# STM32_microcontroller_RF.net
KiCad netlist of a schematic drawn in Altium Designer
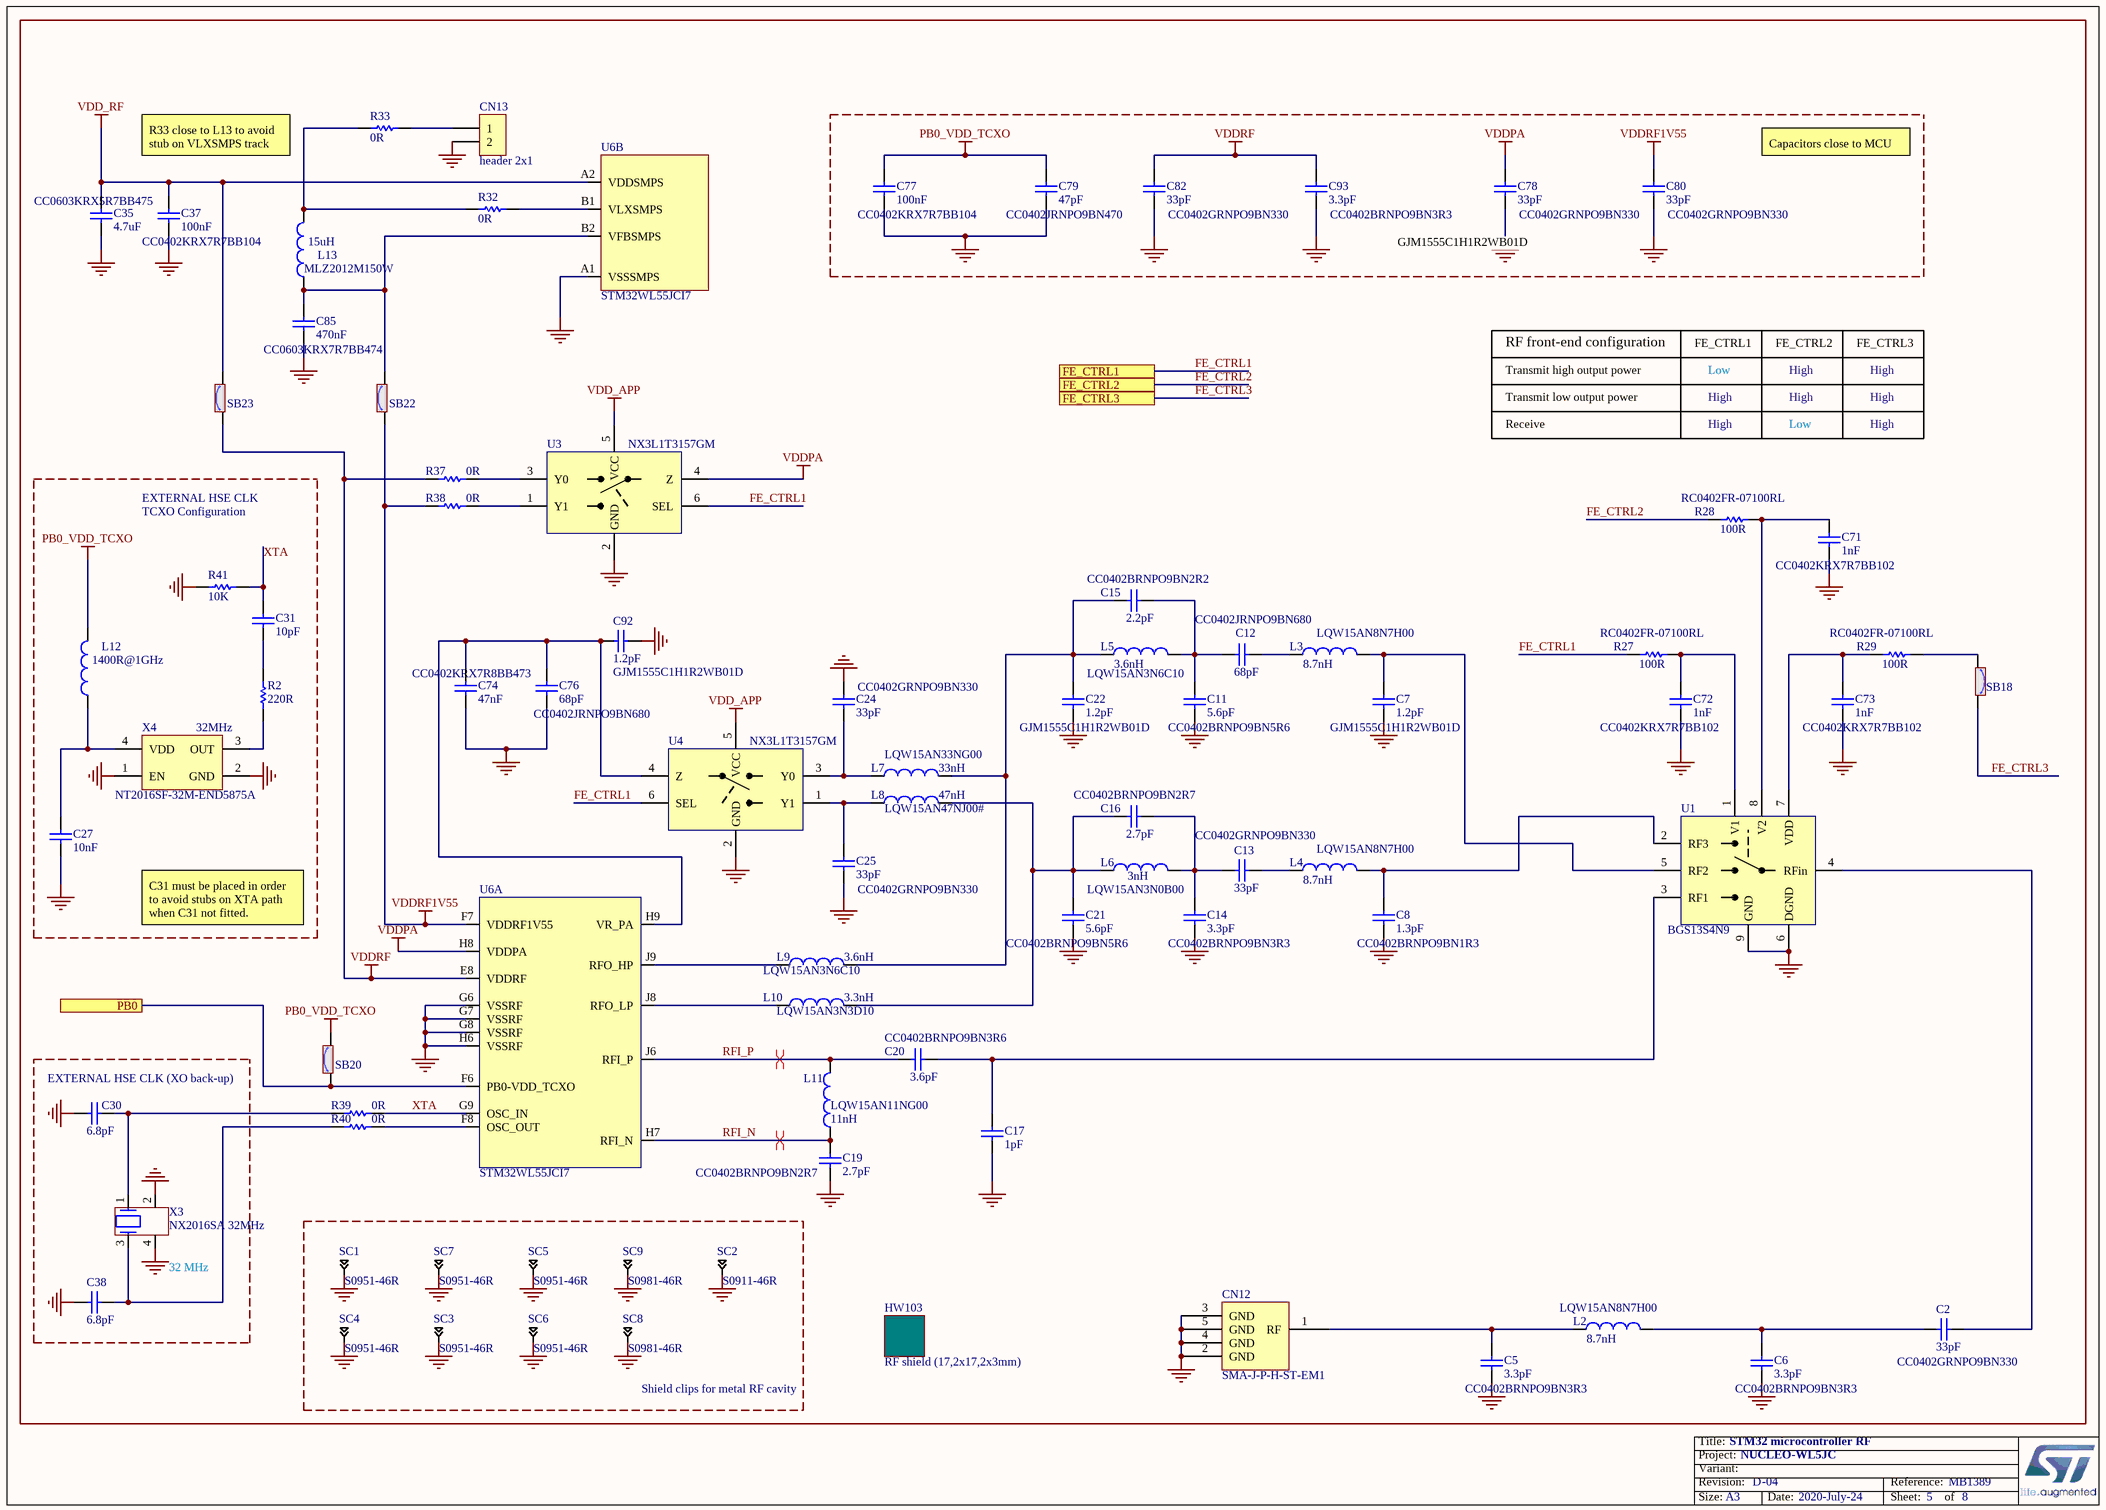
[diagram p0: STM32_microcontroller_RF.SchDoc]

(export (version "E")
  (design (tool "Eeschema 10.0.6"))
  (components
    (comp (ref "C2")
      (value "33pF")
      (footprint "C0402")
      (description "Capacitor, MLCC, 33pF, 50V, NPO, +/-2%, 0402, T=0,5mm")
      (fields
        (field (name "INTERNAL_PART_NUMBER") "MCD-01784")
        (field (name "MANUFACTURER_PART_NUMBER") "CC0402GRNPO9BN330")
        (field (name "MANUFACTURER") "YAGEO")
        (field (name "PROVIDED_BY") "SUBCO")
      )
      (libsource (lib "MCD_PARTS_database") (part "Capacitor"))
    )
    (comp (ref "C5")
      (value "3.3pF")
      (footprint "C0402")
      (description "Capacitor, MLCC, 3.3pF, 50V, NPO, +/-0.1pF, 0402, T=0,5mm")
      (fields
        (field (name "INTERNAL_PART_NUMBER") "MCD-01775")
        (field (name "MANUFACTURER_PART_NUMBER") "CC0402BRNPO9BN3R3")
        (field (name "MANUFACTURER") "YAGEO")
        (field (name "PROVIDED_BY") "SUBCO")
      )
      (libsource (lib "MCD_PARTS_database") (part "Capacitor"))
    )
    (comp (ref "C6")
      (value "3.3pF")
      (footprint "C0402")
      (description "Capacitor, MLCC, 3.3pF, 50V, NPO, +/-0.1pF, 0402, T=0,5mm")
      (fields
        (field (name "INTERNAL_PART_NUMBER") "MCD-01775")
        (field (name "MANUFACTURER_PART_NUMBER") "CC0402BRNPO9BN3R3")
        (field (name "MANUFACTURER") "YAGEO")
        (field (name "PROVIDED_BY") "SUBCO")
      )
      (libsource (lib "MCD_PARTS_database") (part "Capacitor"))
    )
    (comp (ref "C7")
      (value "1.2pF")
      (footprint "C0402")
      (description "Capacitor, High Q type for high frequency and high power, SMD, 1.2pF, 50V, 0,05pf, 0402")
      (fields
        (field (name "INTERNAL_PART_NUMBER") "MCD-02065")
        (field (name "MANUFACTURER") "MURATA")
        (field (name "MANUFACTURER_PART_NUMBER") "GJM1555C1H1R2WB01D")
      )
      (libsource (lib "MCD_PARTS_database") (part "Capacitor"))
    )
    (comp (ref "C8")
      (value "1.3pF")
      (footprint "C0402")
      (description "Capacitor, MLCC, 1.3pF, 50V, NPO, +/-0.1pF, 0402, T=0,5mm")
      (fields
        (field (name "INTERNAL_PART_NUMBER") "MCD-01772")
        (field (name "MANUFACTURER_PART_NUMBER") "CC0402BRNPO9BN1R3")
        (field (name "MANUFACTURER") "YAGEO")
        (field (name "PROVIDED_BY") "SUBCO")
      )
      (libsource (lib "MCD_PARTS_database") (part "Capacitor"))
    )
    (comp (ref "C11")
      (value "5.6pF")
      (footprint "C0402")
      (description "Capacitor, MLCC, 5.6pF, 50V, NPO, +/- 0.1pF, 0402, T=0,5mm")
      (fields
        (field (name "INTERNAL_PART_NUMBER") "MCD-01374")
        (field (name "MANUFACTURER") "YAGEO")
        (field (name "MANUFACTURER_PART_NUMBER") "CC0402BRNPO9BN5R6")
      )
      (libsource (lib "MCD_PARTS_database") (part "Capacitor"))
    )
    (comp (ref "C12")
      (value "68pF")
      (footprint "C0402")
      (description "Capacitor, MLCC, 68pF, 50V, NPO, +/-5%, 0402, T=0,5mm")
      (fields
        (field (name "INTERNAL_PART_NUMBER") "MCD-01604")
        (field (name "MANUFACTURER") "YAGEO")
        (field (name "MANUFACTURER_PART_NUMBER") "CC0402JRNPO9BN680")
      )
      (libsource (lib "MCD_PARTS_database") (part "Capacitor"))
    )
    (comp (ref "C13")
      (value "33pF")
      (footprint "C0402")
      (description "Capacitor, MLCC, 33pF, 50V, NPO, +/-2%, 0402, T=0,5mm")
      (fields
        (field (name "INTERNAL_PART_NUMBER") "MCD-01784")
        (field (name "MANUFACTURER_PART_NUMBER") "CC0402GRNPO9BN330")
        (field (name "MANUFACTURER") "YAGEO")
        (field (name "PROVIDED_BY") "SUBCO")
      )
      (libsource (lib "MCD_PARTS_database") (part "Capacitor"))
    )
    (comp (ref "C14")
      (value "3.3pF")
      (footprint "C0402")
      (description "Capacitor, MLCC, 3.3pF, 50V, NPO, +/-0.1pF, 0402, T=0,5mm")
      (fields
        (field (name "INTERNAL_PART_NUMBER") "MCD-01775")
        (field (name "MANUFACTURER_PART_NUMBER") "CC0402BRNPO9BN3R3")
        (field (name "MANUFACTURER") "YAGEO")
        (field (name "PROVIDED_BY") "SUBCO")
      )
      (libsource (lib "MCD_PARTS_database") (part "Capacitor"))
    )
    (comp (ref "C15")
      (value "2.2pF")
      (footprint "C0402")
      (description "Capacitor, MLCC, 2.2pF, 50V, NPO, +/-0.1pF, 0402, T=0,5mm")
      (fields
        (field (name "INTERNAL_PART_NUMBER") "MCD-01773")
        (field (name "MANUFACTURER") "YAGEO")
        (field (name "MANUFACTURER_PART_NUMBER") "CC0402BRNPO9BN2R2")
      )
      (libsource (lib "MCD_PARTS_database") (part "Capacitor"))
    )
    (comp (ref "C16")
      (value "2.7pF")
      (footprint "C0402")
      (description "Capacitor, MLCC, 2.7pF, 50V, NPO, +/-0.1pF, 0402, T=0,5mm")
      (fields
        (field (name "INTERNAL_PART_NUMBER") "MCD-01774")
        (field (name "MANUFACTURER_PART_NUMBER") "CC0402BRNPO9BN2R7")
        (field (name "MANUFACTURER") "YAGEO")
        (field (name "PROVIDED_BY") "SUBCO")
      )
      (libsource (lib "MCD_PARTS_database") (part "Capacitor"))
    )
    (comp (ref "C17")
      (value "1pF")
      (footprint "C0402")
      (description "Capacitor, MLCC, 1pF, 50V, NPO, +/-0.1pF, 0402, T=0,5mm")
      (fields (field (name "INTERNAL_PART_NUMBER") "MCD-01600") (field (name "MANUFACTURER") "YAGEO"))
      (libsource (lib "MCD_PARTS_database") (part "Capacitor"))
    )
    (comp (ref "C19")
      (value "2.7pF")
      (footprint "C0402")
      (description "Capacitor, MLCC, 2.7pF, 50V, NPO, +/-0.1pF, 0402, T=0,5mm")
      (fields
        (field (name "INTERNAL_PART_NUMBER") "MCD-01774")
        (field (name "MANUFACTURER_PART_NUMBER") "CC0402BRNPO9BN2R7")
        (field (name "MANUFACTURER") "YAGEO")
        (field (name "PROVIDED_BY") "SUBCO")
      )
      (libsource (lib "MCD_PARTS_database") (part "Capacitor"))
    )
    (comp (ref "C20")
      (value "3.6pF")
      (footprint "C0402")
      (description "Capacitor, MLCC, 3.6pF, 50V, NPO, +/-0.1pF, 0402, T=0,5mm")
      (fields
        (field (name "INTERNAL_PART_NUMBER") "MCD-01776")
        (field (name "MANUFACTURER_PART_NUMBER") "CC0402BRNPO9BN3R6")
        (field (name "MANUFACTURER") "YAGEO")
        (field (name "PROVIDED_BY") "SUBCO")
      )
      (libsource (lib "MCD_PARTS_database") (part "Capacitor"))
    )
    (comp (ref "C21")
      (value "5.6pF")
      (footprint "C0402")
      (description "Capacitor, MLCC, 5.6pF, 50V, NPO, +/- 0.1pF, 0402, T=0,5mm")
      (fields
        (field (name "INTERNAL_PART_NUMBER") "MCD-01374")
        (field (name "MANUFACTURER_PART_NUMBER") "CC0402BRNPO9BN5R6")
        (field (name "MANUFACTURER") "YAGEO")
        (field (name "PROVIDED_BY") "SUBCO")
      )
      (libsource (lib "MCD_PARTS_database") (part "Capacitor"))
    )
    (comp (ref "C22")
      (value "1.2pF")
      (footprint "C0402")
      (description "Capacitor, High Q type for high frequency and high power, SMD, 1.2pF, 50V, 0,05pf, 0402")
      (fields
        (field (name "INTERNAL_PART_NUMBER") "MCD-02065")
        (field (name "MANUFACTURER") "MURATA")
        (field (name "MANUFACTURER_PART_NUMBER") "GJM1555C1H1R2WB01D")
      )
      (libsource (lib "MCD_PARTS_database") (part "Capacitor"))
    )
    (comp (ref "C24")
      (value "33pF")
      (footprint "C0402")
      (description "Capacitor, MLCC, 33pF, 50V, NPO, +/-2%, 0402, T=0,5mm")
      (fields
        (field (name "INTERNAL_PART_NUMBER") "MCD-01784")
        (field (name "MANUFACTURER_PART_NUMBER") "CC0402GRNPO9BN330")
        (field (name "MANUFACTURER") "YAGEO")
        (field (name "PROVIDED_BY") "SUBCO")
      )
      (libsource (lib "MCD_PARTS_database") (part "Capacitor"))
    )
    (comp (ref "C25")
      (value "33pF")
      (footprint "C0402")
      (description "Capacitor, MLCC, 33pF, 50V, NPO, +/-2%, 0402, T=0,5mm")
      (fields
        (field (name "INTERNAL_PART_NUMBER") "MCD-01784")
        (field (name "MANUFACTURER_PART_NUMBER") "CC0402GRNPO9BN330")
        (field (name "MANUFACTURER") "YAGEO")
        (field (name "PROVIDED_BY") "SUBCO")
      )
      (libsource (lib "MCD_PARTS_database") (part "Capacitor"))
    )
    (comp (ref "C27")
      (value "10nF")
      (footprint "C0402")
      (description "Capacitor, MLCC, 10nF, 16V, X7R, 10%, 0402, T=0.5mm")
      (fields
        (field (name "INTERNAL_PART_NUMBER") "MCD-00011")
        (field (name "MANUFACTURER_PART_NUMBER") "CC0402KRX7R7BB103")
        (field (name "PROVIDED_BY") "SUBCO")
      )
      (libsource (lib "MCD_PARTS_database") (part "Capacitor"))
    )
    (comp (ref "C30")
      (value "6.8pF")
      (footprint "C0402")
      (description "Capacitor, MLCC, 6.8pF, 50V, NPO, +-0.25pF, 0402, T=0.5mm")
      (fields
        (field (name "INTERNAL_PART_NUMBER") "MCD-00674")
        (field (name "MANUFACTURER_PART_NUMBER") "CC0402CRNPO9BN6R8")
        (field (name "PROVIDED_BY") "SUBCO")
      )
      (libsource (lib "MCD_PARTS_database") (part "Capacitor"))
    )
    (comp (ref "C31")
      (value "10pF")
      (footprint "C0402")
      (description "Capacitor, MLCC, 10pF, 50V, NPO, +/-5%, 0402, T=0,5mm")
      (fields (field (name "INTERNAL_PART_NUMBER") "MCD-00015") (field (name "MANUFACTURER") "YAGEO"))
      (libsource (lib "MCD_PARTS_database") (part "Capacitor"))
    )
    (comp (ref "C35")
      (value "4.7uF")
      (footprint "C0603")
      (description "Capacitor, MLCC, 4.7uF, 16V, X5R, 10%, 0603, T=0.8mm")
      (fields
        (field (name "INTERNAL_PART_NUMBER") "MCD-00009")
        (field (name "MANUFACTURER_PART_NUMBER") "CC0603KRX5R7BB475")
        (field (name "MANUFACTURER") "YAGEO")
        (field (name "PROVIDED_BY") "SUBCO")
      )
      (libsource (lib "MCD_PARTS_database") (part "Capacitor"))
    )
    (comp (ref "C37")
      (value "100nF")
      (footprint "C0402")
      (description "Capacitor, MLCC, 100nF, 16V, X7R, 10%, 0402, T=0,5mm")
      (fields
        (field (name "INTERNAL_PART_NUMBER") "MCD-00102")
        (field (name "MANUFACTURER_PART_NUMBER") "CC0402KRX7R7BB104")
        (field (name "MANUFACTURER") "YAGEO")
        (field (name "PROVIDED_BY") "SUBCO")
      )
      (libsource (lib "MCD_PARTS_database") (part "Capacitor"))
    )
    (comp (ref "C38")
      (value "6.8pF")
      (footprint "C0402")
      (description "Capacitor, MLCC, 6.8pF, 50V, NPO, +-0.25pF, 0402, T=0.5mm")
      (fields
        (field (name "INTERNAL_PART_NUMBER") "MCD-00674")
        (field (name "MANUFACTURER_PART_NUMBER") "CC0402CRNPO9BN6R8")
        (field (name "PROVIDED_BY") "SUBCO")
      )
      (libsource (lib "MCD_PARTS_database") (part "Capacitor"))
    )
    (comp (ref "C71")
      (value "1nF")
      (footprint "C0402")
      (description "Capacitor, MLCC, 1nF, 16V, X7R, 10%, 0402, T=0.5mm")
      (fields
        (field (name "INTERNAL_PART_NUMBER") "MCD-00198")
        (field (name "MANUFACTURER_PART_NUMBER") "CC0402KRX7R7BB102")
        (field (name "MANUFACTURER") "YAGEO")
        (field (name "PROVIDED_BY") "SUBCO")
      )
      (libsource (lib "MCD_PARTS_database") (part "Capacitor"))
    )
    (comp (ref "C72")
      (value "1nF")
      (footprint "C0402")
      (description "Capacitor, MLCC, 1nF, 16V, X7R, 10%, 0402, T=0.5mm")
      (fields
        (field (name "INTERNAL_PART_NUMBER") "MCD-00198")
        (field (name "MANUFACTURER_PART_NUMBER") "CC0402KRX7R7BB102")
        (field (name "MANUFACTURER") "YAGEO")
        (field (name "PROVIDED_BY") "SUBCO")
      )
      (libsource (lib "MCD_PARTS_database") (part "Capacitor"))
    )
    (comp (ref "C73")
      (value "1nF")
      (footprint "C0402")
      (description "Capacitor, MLCC, 1nF, 16V, X7R, 10%, 0402, T=0.5mm")
      (fields
        (field (name "INTERNAL_PART_NUMBER") "MCD-00198")
        (field (name "MANUFACTURER_PART_NUMBER") "CC0402KRX7R7BB102")
        (field (name "MANUFACTURER") "YAGEO")
        (field (name "PROVIDED_BY") "SUBCO")
      )
      (libsource (lib "MCD_PARTS_database") (part "Capacitor"))
    )
    (comp (ref "C74")
      (value "47nF")
      (footprint "C0402")
      (description "Capacitor, MLCC, 47nF, 25V, X7R, +-10%, 0402, T=0,5mm")
      (fields
        (field (name "INTERNAL_PART_NUMBER") "MCD-01605")
        (field (name "MANUFACTURER_PART_NUMBER") "CC0402KRX7R8BB473")
        (field (name "MANUFACTURER") "YAGEO")
        (field (name "PROVIDED_BY") "SUBCO")
      )
      (libsource (lib "MCD_PARTS_database") (part "Capacitor"))
    )
    (comp (ref "C76")
      (value "68pF")
      (footprint "C0402")
      (description "Capacitor, MLCC, 68pF, 50V, NPO, +-5%, 0402, T=0,5mm")
      (fields
        (field (name "INTERNAL_PART_NUMBER") "MCD-01604")
        (field (name "MANUFACTURER_PART_NUMBER") "CC0402JRNPO9BN680")
        (field (name "MANUFACTURER") "YAGEO")
        (field (name "PROVIDED_BY") "SUBCO")
      )
      (libsource (lib "MCD_PARTS_database") (part "Capacitor"))
    )
    (comp (ref "C77")
      (value "100nF")
      (footprint "C0402")
      (description "Capacitor, MLCC, 100nF, 16V, X7R, 10%, 0402, T=0,5mm")
      (fields
        (field (name "INTERNAL_PART_NUMBER") "MCD-00102")
        (field (name "MANUFACTURER_PART_NUMBER") "CC0402KRX7R7BB104")
        (field (name "MANUFACTURER") "YAGEO")
        (field (name "PROVIDED_BY") "SUBCO")
      )
      (libsource (lib "MCD_PARTS_database") (part "Capacitor"))
    )
    (comp (ref "C78")
      (value "33pF")
      (footprint "C0402")
      (description "Capacitor, MLCC, 33pF, 50V, NPO, +/-2%, 0402, T=0,5mm")
      (fields
        (field (name "INTERNAL_PART_NUMBER") "MCD-01784")
        (field (name "MANUFACTURER_PART_NUMBER") "CC0402GRNPO9BN330")
        (field (name "MANUFACTURER") "YAGEO")
        (field (name "PROVIDED_BY") "SUBCO")
      )
      (libsource (lib "MCD_PARTS_database") (part "Capacitor"))
    )
    (comp (ref "C79")
      (value "47pF")
      (footprint "C0402")
      (description "Capacitor, MLCC, 147pF, 50V, NPO, +-5%, 0402, T=0,5mm")
      (fields
        (field (name "INTERNAL_PART_NUMBER") "MCD-01603")
        (field (name "MANUFACTURER_PART_NUMBER") "CC0402JRNPO9BN470")
        (field (name "MANUFACTURER") "YAGEO")
        (field (name "PROVIDED_BY") "SUBCO")
      )
      (libsource (lib "MCD_PARTS_database") (part "Capacitor"))
    )
    (comp (ref "C80")
      (value "33pF")
      (footprint "C0402")
      (description "Capacitor, MLCC, 33pF, 50V, NPO, +/-2%, 0402, T=0,5mm")
      (fields
        (field (name "INTERNAL_PART_NUMBER") "MCD-01784")
        (field (name "MANUFACTURER_PART_NUMBER") "CC0402GRNPO9BN330")
        (field (name "MANUFACTURER") "YAGEO")
        (field (name "PROVIDED_BY") "SUBCO")
      )
      (libsource (lib "MCD_PARTS_database") (part "Capacitor"))
    )
    (comp (ref "C82")
      (value "33pF")
      (footprint "C0402")
      (description "Capacitor, MLCC, 33pF, 50V, NPO, +/-2%, 0402, T=0,5mm")
      (fields
        (field (name "INTERNAL_PART_NUMBER") "MCD-01784")
        (field (name "MANUFACTURER_PART_NUMBER") "CC0402GRNPO9BN330")
        (field (name "MANUFACTURER") "YAGEO")
        (field (name "PROVIDED_BY") "SUBCO")
      )
      (libsource (lib "MCD_PARTS_database") (part "Capacitor"))
    )
    (comp (ref "C85")
      (value "470nF")
      (footprint "C0603")
      (description "Capacitor, MLCC, 470nF, 16V, X7R, 10%, 0603, T=0.8mm")
      (fields
        (field (name "INTERNAL_PART_NUMBER") "MCD-01006")
        (field (name "MANUFACTURER_PART_NUMBER") "CC0603KRX7R7BB474")
        (field (name "MANUFACTURER") "YAGEO")
        (field (name "PROVIDED_BY") "SUBCO")
      )
      (libsource (lib "MCD_PARTS_database") (part "Capacitor"))
    )
    (comp (ref "C92")
      (value "1.2pF")
      (footprint "C0402")
      (description "Capacitor, High Q type for high frequency and high power, SMD, 1.2pF, 50V, 0,05pf, 0402")
      (fields
        (field (name "INTERNAL_PART_NUMBER") "MCD-02065")
        (field (name "MANUFACTURER") "MURATA")
        (field (name "MANUFACTURER_PART_NUMBER") "GJM1555C1H1R2WB01D")
      )
      (libsource (lib "MCD_PARTS_database") (part "Capacitor"))
    )
    (comp (ref "C93")
      (value "3.3pF")
      (footprint "C0402")
      (description "Capacitor, MLCC, 3.3pF, 50V, NPO, +/-0.1pF, 0402, T=0,5mm")
      (fields
        (field (name "INTERNAL_PART_NUMBER") "MCD-01775")
        (field (name "MANUFACTURER") "YAGEO")
        (field (name "MANUFACTURER_PART_NUMBER") "CC0402BRNPO9BN3R3")
      )
      (libsource (lib "MCD_PARTS_database") (part "Capacitor"))
    )
    (comp (ref "CN12")
      (value "SMA-J-P-H-ST-EM1")
      (footprint "CON_SAMTEC_SMA-J-P-X-ST-EM1")
      (description "RF SMA connector PCB edge")
      (fields
        (field (name "INTERNAL_PART_NUMBER") "MCD-00279")
        (field (name "MANUFACTURER") "SAMTEC")
        (field (name "PROVIDED_BY") "SUBCO")
      )
      (libsource (lib "MCD_PARTS_database") (part "SMA-J-P-H-ST-EM1"))
    )
    (comp (ref "CN13")
      (value "header 2x1")
      (footprint "CON_988-JIUBABA_PHFS25-11-02-G0B115-T-1")
      (description "Header, 2x1, 2.54mm, VR, TH, Height 6mm/3mm")
      (fields
        (field (name "INTERNAL_PART_NUMBER") "MCD-00314")
        (field (name "MANUFACTURER_PART_NUMBER") "PHFS25-11-02-G0B115-T-1")
        (field (name "PROVIDED_BY") "SUBCO")
      )
      (libsource (lib "MCD_PARTS_database") (part "Header 2x1"))
    )
    (comp (ref "HW103")
      (value "RF shield (17,2x17,2x3mm)")
      (footprint "SHIELD_RF_ST-CUSTOM_17P2X17P2_H3")
      (description "RF shield (17,2x17,2x3mm), Brass with Sn finishing, Sheet tickness : 0,2mm")
      (fields (field (name "INTERNAL_PART_NUMBER") "MCD-02088") (field (name "BMS_PART_NUMBER") "TBD"))
      (libsource (lib "MCD_PARTS_database") (part "Daughter_Board"))
    )
    (comp (ref "L2")
      (value "8.7nH")
      (footprint "IND_0402_MURATA_LQW15AN_H0P5")
      (description "0402 inductor, 8.7nH +/-3%, 540mA max, 0.14 ohm DC max, Q min = 25")
      (fields
        (field (name "INTERNAL_PART_NUMBER") "MCD-01768")
        (field (name "MANUFACTURER_PART_NUMBER") "LQW15AN8N7H00")
        (field (name "MANUFACTURER") "MURATA")
        (field (name "PROVIDED_BY") "SUBCO")
      )
      (libsource (lib "MCD_PARTS_database") (part "Inductor"))
    )
    (comp (ref "L3")
      (value "8.7nH")
      (footprint "IND_0402_MURATA_LQW15AN_H0P5")
      (description "0402 inductor, 8.7nH +/-3%, 540mA max, 0.14 ohm DC max, Q min = 25")
      (fields
        (field (name "INTERNAL_PART_NUMBER") "MCD-01768")
        (field (name "MANUFACTURER") "MURATA")
        (field (name "MANUFACTURER_PART_NUMBER") "LQW15AN8N7H00")
      )
      (libsource (lib "MCD_PARTS_database") (part "Inductor"))
    )
    (comp (ref "L4")
      (value "8.7nH")
      (footprint "IND_0402_MURATA_LQW15AN_H0P5")
      (description "0402 inductor, 8.7nH +/-3%, 540mA max, 0.14 ohm DC max, Q min = 25")
      (fields
        (field (name "INTERNAL_PART_NUMBER") "MCD-01768")
        (field (name "MANUFACTURER_PART_NUMBER") "LQW15AN8N7H00")
        (field (name "MANUFACTURER") "MURATA")
        (field (name "PROVIDED_BY") "SUBCO")
      )
      (libsource (lib "MCD_PARTS_database") (part "Inductor"))
    )
    (comp (ref "L5")
      (value "3.6nH")
      (footprint "IND_0402_MURATA_LQW15AN_H0P5")
      (description "0402 inductor, 3.6nH +/-0.2nH, 900mA max, 0.04 ohm DC max, Q min = 30")
      (fields
        (field (name "INTERNAL_PART_NUMBER") "MCD-01762")
        (field (name "MANUFACTURER") "MURATA")
        (field (name "MANUFACTURER_PART_NUMBER") "LQW15AN3N6C10")
      )
      (libsource (lib "MCD_PARTS_database") (part "Inductor"))
    )
    (comp (ref "L6")
      (value "3nH")
      (footprint "IND_0402_MURATA_LQW15AN_H0P5")
      (description "0402 inductor, 3nH +-0.1nH, 750mA max, 0.07 ohm DC max, Q min = 20")
      (fields
        (field (name "INTERNAL_PART_NUMBER") "MCD-01922")
        (field (name "MANUFACTURER_PART_NUMBER") "LQW15AN3N0B00")
        (field (name "MANUFACTURER") "MURATA")
        (field (name "PROVIDED_BY") "SUBCO")
      )
      (libsource (lib "MCD_PARTS_database") (part "Inductor"))
    )
    (comp (ref "L7")
      (value "33nH")
      (footprint "IND_0402_MURATA_LQW15AN_H0P5")
      (description "Inductor, 33nH +/-2%, 260mA max , 0.63 ohm DC max, 0402, Q min = 25.")
      (fields
        (field (name "INTERNAL_PART_NUMBER") "MCD-02069")
        (field (name "MANUFACTURER") "MURATA")
        (field (name "MANUFACTURER_PART_NUMBER") "LQW15AN33NG00")
      )
      (libsource (lib "MCD_PARTS_database") (part "Inductor"))
    )
    (comp (ref "L8")
      (value "47nH")
      (footprint "IND_0402_MURATA_LQW15AN2N4C00X")
      (description "Inductor, 47nH, +-5%, 210mA, 1.08ohm DC max, 0402")
      (fields
        (field (name "INTERNAL_PART_NUMBER") "MCD-01609")
        (field (name "MANUFACTURER_PART_NUMBER") "LQW15AN47NJ00#")
        (field (name "MANUFACTURER") "MURATA")
        (field (name "PROVIDED_BY") "SUBCO")
      )
      (libsource (lib "MCD_PARTS_database") (part "Inductor"))
    )
    (comp (ref "L9")
      (value "3.6nH")
      (footprint "IND_0402_MURATA_LQW15AN_H0P5")
      (description "0402 inductor, 3.6nH +/-0.2nH, 900mA max, 0.04 ohm DC max, Q min = 30")
      (fields
        (field (name "INTERNAL_PART_NUMBER") "MCD-01762")
        (field (name "MANUFACTURER_PART_NUMBER") "LQW15AN3N6C10")
        (field (name "MANUFACTURER") "MURATA")
        (field (name "PROVIDED_BY") "SUBCO")
      )
      (libsource (lib "MCD_PARTS_database") (part "Inductor"))
    )
    (comp (ref "L10")
      (value "3.3nH")
      (footprint "IND_0402_MURATA_LQW15AN_H0P5")
      (description "0402 inductor, 3.3nH +-0.5nH, 900mA max, 0.04 ohm DC max, Q min = 30")
      (fields
        (field (name "INTERNAL_PART_NUMBER") "MCD-01761")
        (field (name "MANUFACTURER_PART_NUMBER") "LQW15AN3N3D10")
        (field (name "MANUFACTURER") "MURATA")
        (field (name "PROVIDED_BY") "SUBCO")
      )
      (libsource (lib "MCD_PARTS_database") (part "Inductor"))
    )
    (comp (ref "L11")
      (value "11nH")
      (footprint "IND_0402_MURATA_LQW15AN_H0P5")
      (description "0402 inductor, 11nH +-2%, 500mA max, 0.14 ohm DC max, Q min = 30")
      (fields
        (field (name "INTERNAL_PART_NUMBER") "MCD-01921")
        (field (name "MANUFACTURER_PART_NUMBER") "LQW15AN11NG00")
        (field (name "MANUFACTURER") "MURATA")
        (field (name "PROVIDED_BY") "SUBCO")
      )
      (libsource (lib "MCD_PARTS_database") (part "Inductor"))
    )
    (comp (ref "L12")
      (value "1400R@1GHz")
      (footprint "IND_0402_MURATA_BLM15H_H0P5")
      (description "ferrite bead, 1400ohms at 1GHz, 250mA, 1.1ohms DC max")
      (fields
        (field (name "INTERNAL_PART_NUMBER") "MCD-01610")
        (field (name "MANUFACTURER_PART_NUMBER") "BLM15HG102SN1#")
        (field (name "PROVIDED_BY") "SUBCO")
      )
      (libsource (lib "MCD_PARTS_database") (part "Inductor"))
    )
    (comp (ref "L13")
      (value "15uH")
      (footprint "IND_TDK_MLZ2012M150W")
      (description "MLZ2012 Multilayer Shielded Inductor 15uH, +/-5%")
      (fields
        (field (name "INTERNAL_PART_NUMBER") "MCD-01433")
        (field (name "MANUFACTURER_PART_NUMBER") "MLZ2012M150W")
        (field (name "MANUFACTURER") "TDK")
        (field (name "PROVIDED_BY") "SUBCO")
      )
      (libsource (lib "MCD_PARTS_database") (part "Inductor"))
    )
    (comp (ref "R2")
      (value "220R")
      (footprint "R0402")
      (description "Resistor,220R,0402,1%,1/16W")
      (fields
        (field (name "INTERNAL_PART_NUMBER") "MCD-00427")
        (field (name "MANUFACTURER_PART_NUMBER") "RC0402FR-07220RL")
        (field (name "PROVIDED_BY") "SUBCO")
      )
      (libsource (lib "MCD_PARTS_database") (part "Resistor"))
    )
    (comp (ref "R27")
      (value "100R")
      (footprint "R0402")
      (description "Resistor,100R,0402,1%,1/16W")
      (fields
        (field (name "INTERNAL_PART_NUMBER") "MCD-00119")
        (field (name "MANUFACTURER_PART_NUMBER") "RC0402FR-07100RL")
        (field (name "MANUFACTURER") "YAGEO")
        (field (name "PROVIDED_BY") "SUBCO")
      )
      (libsource (lib "MCD_PARTS_database") (part "Resistor"))
    )
    (comp (ref "R28")
      (value "100R")
      (footprint "R0402")
      (description "Resistor,100R,0402,1%,1/16W")
      (fields
        (field (name "INTERNAL_PART_NUMBER") "MCD-00119")
        (field (name "MANUFACTURER_PART_NUMBER") "RC0402FR-07100RL")
        (field (name "MANUFACTURER") "YAGEO")
        (field (name "PROVIDED_BY") "SUBCO")
      )
      (libsource (lib "MCD_PARTS_database") (part "Resistor"))
    )
    (comp (ref "R29")
      (value "100R")
      (footprint "R0402")
      (description "Resistor,100R,0402,1%,1/16W")
      (fields
        (field (name "INTERNAL_PART_NUMBER") "MCD-00119")
        (field (name "MANUFACTURER_PART_NUMBER") "RC0402FR-07100RL")
        (field (name "MANUFACTURER") "YAGEO")
        (field (name "PROVIDED_BY") "SUBCO")
      )
      (libsource (lib "MCD_PARTS_database") (part "Resistor"))
    )
    (comp (ref "R32")
      (value "0R")
      (footprint "R0402")
      (description "Resistor,0R,0402,5%,1/16W")
      (fields
        (field (name "INTERNAL_PART_NUMBER") "MCD-00052")
        (field (name "MANUFACTURER_PART_NUMBER") "RC0402JR-070RL")
        (field (name "PROVIDED_BY") "SUBCO")
      )
      (libsource (lib "MCD_PARTS_database") (part "Resistor"))
    )
    (comp (ref "R33")
      (value "0R")
      (footprint "R0402")
      (description "Resistor,0R,0402,5%,1/16W")
      (fields
        (field (name "INTERNAL_PART_NUMBER") "MCD-00052")
        (field (name "MANUFACTURER_PART_NUMBER") "RC0402JR-070RL")
        (field (name "PROVIDED_BY") "SUBCO")
      )
      (libsource (lib "MCD_PARTS_database") (part "Resistor"))
    )
    (comp (ref "R37")
      (value "0R")
      (footprint "R0402")
      (description "Resistor,0R,0402,5%,1/16W")
      (fields
        (field (name "INTERNAL_PART_NUMBER") "MCD-00052")
        (field (name "MANUFACTURER_PART_NUMBER") "RC0402JR-070RL")
        (field (name "PROVIDED_BY") "SUBCO")
      )
      (libsource (lib "MCD_PARTS_database") (part "Resistor"))
    )
    (comp (ref "R38")
      (value "0R")
      (footprint "R0402")
      (description "Resistor,0R,0402,5%,1/16W")
      (fields
        (field (name "INTERNAL_PART_NUMBER") "MCD-00052")
        (field (name "MANUFACTURER_PART_NUMBER") "RC0402JR-070RL")
        (field (name "PROVIDED_BY") "SUBCO")
      )
      (libsource (lib "MCD_PARTS_database") (part "Resistor"))
    )
    (comp (ref "R39")
      (value "0R")
      (footprint "R0402")
      (description "Resistor,0R,0402,5%,1/16W")
      (fields
        (field (name "INTERNAL_PART_NUMBER") "MCD-00052")
        (field (name "MANUFACTURER_PART_NUMBER") "RC0402JR-070RL")
        (field (name "PROVIDED_BY") "SUBCO")
      )
      (libsource (lib "MCD_PARTS_database") (part "Resistor"))
    )
    (comp (ref "R40")
      (value "0R")
      (footprint "R0402")
      (description "Resistor,0R,0402,5%,1/16W")
      (fields
        (field (name "INTERNAL_PART_NUMBER") "MCD-00052")
        (field (name "MANUFACTURER_PART_NUMBER") "RC0402JR-070RL")
        (field (name "PROVIDED_BY") "SUBCO")
      )
      (libsource (lib "MCD_PARTS_database") (part "Resistor"))
    )
    (comp (ref "R41")
      (value "10K")
      (footprint "R0402")
      (description "Resistor,10K,0402,1%,1/16W")
      (fields
        (field (name "INTERNAL_PART_NUMBER") "MCD-00053")
        (field (name "MANUFACTURER_PART_NUMBER") "RC0402FR-0710KL")
        (field (name "PROVIDED_BY") "SUBCO")
      )
      (libsource (lib "MCD_PARTS_database") (part "Resistor"))
    )
    (comp (ref "SB18")
      (value "~")
      (footprint "SOLDER-BRIDGE_R0603-0R")
      (description "Solder Bridge ON")
      (fields
        (field (name "INTERNAL_PART_NUMBER") "MCD-00071")
        (field (name "MANUFACTURER_PART_NUMBER") "RC0603JR-070RL")
        (field (name "PROVIDED_BY") "SUBCO")
      )
      (libsource (lib "") (part "SB_ON_1"))
    )
    (comp (ref "SB20")
      (value "~")
      (footprint "SOLDER-BRIDGE_R0603-0R")
      (description "Solder Bridge ON")
      (fields
        (field (name "INTERNAL_PART_NUMBER") "MCD-00071")
        (field (name "MANUFACTURER_PART_NUMBER") "RC0603JR-070RL")
        (field (name "PROVIDED_BY") "SUBCO")
      )
      (libsource (lib "MCD_PARTS_database") (part "SB_ON"))
    )
    (comp (ref "SB22")
      (value "~")
      (footprint "SOLDER-BRIDGE_R0603-0R")
      (description "Solder Bridge ON")
      (fields
        (field (name "INTERNAL_PART_NUMBER") "MCD-00071")
        (field (name "MANUFACTURER_PART_NUMBER") "RC0603JR-070RL")
        (field (name "PROVIDED_BY") "SUBCO")
      )
      (libsource (lib "MCD_PARTS_database") (part "SB_ON"))
    )
    (comp (ref "SB23")
      (value "~")
      (footprint "SOLDER-BRIDGE_R0603-0R")
      (description "Solder Bridge ON")
      (fields
        (field (name "INTERNAL_PART_NUMBER") "MCD-00071")
        (field (name "MANUFACTURER_PART_NUMBER") "RC0603JR-070RL")
        (field (name "PROVIDED_BY") "SUBCO")
      )
      (libsource (lib "MCD_PARTS_database") (part "SB_ON"))
    )
    (comp (ref "SC1")
      (value "S0951-46R")
      (footprint "CLIP_HARWIN_S0951-46R")
      (description "shield clip Harwin S0951-46R to fix RF shielded cavity")
      (fields
        (field (name "INTERNAL_PART_NUMBER") "MCD-01587")
        (field (name "MANUFACTURER") "HARWIN")
        (field (name "PROVIDED_BY") "SUBCO")
      )
      (libsource (lib "MCD_PARTS_database") (part "Shield-clip_S0951-46R"))
    )
    (comp (ref "SC2")
      (value "S0911-46R")
      (description "shield clip Harwin S0911-46R to fix RF shielded cavity - SMT RFI Shield Clip, Compact (T+R)")
      (fields
        (field (name "INTERNAL_PART_NUMBER") "MCD-02165")
        (field (name "MANUFACTURER") "HARWIN")
        (field (name "PROVIDED_BY") "SUBCO")
      )
      (libsource (lib "MCD_PARTS_database") (part "Shield-clip_S0951-46R"))
    )
    (comp (ref "SC3")
      (value "S0951-46R")
      (footprint "CLIP_HARWIN_S0951-46R")
      (description "shield clip Harwin S0951-46R to fix RF shielded cavity")
      (fields
        (field (name "INTERNAL_PART_NUMBER") "MCD-01587")
        (field (name "MANUFACTURER") "HARWIN")
        (field (name "PROVIDED_BY") "SUBCO")
      )
      (libsource (lib "MCD_PARTS_database") (part "Shield-clip_S0951-46R"))
    )
    (comp (ref "SC4")
      (value "S0951-46R")
      (footprint "CLIP_HARWIN_S0951-46R")
      (description "shield clip Harwin S0951-46R to fix RF shielded cavity")
      (fields
        (field (name "INTERNAL_PART_NUMBER") "MCD-01587")
        (field (name "MANUFACTURER") "HARWIN")
        (field (name "PROVIDED_BY") "SUBCO")
      )
      (libsource (lib "MCD_PARTS_database") (part "Shield-clip_S0951-46R"))
    )
    (comp (ref "SC5")
      (value "S0951-46R")
      (footprint "CLIP_HARWIN_S0951-46R")
      (description "shield clip Harwin S0951-46R to fix RF shielded cavity")
      (fields
        (field (name "INTERNAL_PART_NUMBER") "MCD-01587")
        (field (name "MANUFACTURER") "HARWIN")
        (field (name "PROVIDED_BY") "SUBCO")
      )
      (libsource (lib "MCD_PARTS_database") (part "Shield-clip_S0951-46R"))
    )
    (comp (ref "SC6")
      (value "S0951-46R")
      (footprint "CLIP_HARWIN_S0951-46R")
      (description "shield clip Harwin S0951-46R to fix RF shielded cavity")
      (fields
        (field (name "INTERNAL_PART_NUMBER") "MCD-01587")
        (field (name "MANUFACTURER") "HARWIN")
        (field (name "PROVIDED_BY") "SUBCO")
      )
      (libsource (lib "MCD_PARTS_database") (part "Shield-clip_S0951-46R"))
    )
    (comp (ref "SC7")
      (value "S0951-46R")
      (footprint "CLIP_HARWIN_S0951-46R")
      (description "shield clip Harwin S0951-46R to fix RF shielded cavity")
      (fields
        (field (name "INTERNAL_PART_NUMBER") "MCD-01587")
        (field (name "MANUFACTURER") "HARWIN")
        (field (name "PROVIDED_BY") "SUBCO")
      )
      (libsource (lib "MCD_PARTS_database") (part "Shield-clip_S0951-46R"))
    )
    (comp (ref "SC8")
      (value "S0981-46R")
      (description "shield clip Harwin S0981-46R to fix RF shielded cavity - SMT RFI Shield Clip, Corner (T+R)")
      (fields
        (field (name "INTERNAL_PART_NUMBER") "MCD-02164")
        (field (name "MANUFACTURER") "HARWIN")
        (field (name "PROVIDED_BY") "SUBCO")
      )
      (libsource (lib "MCD_PARTS_database") (part "Shield-clip_S0951-46R"))
    )
    (comp (ref "SC9")
      (value "S0981-46R")
      (description "shield clip Harwin S0981-46R to fix RF shielded cavity - SMT RFI Shield Clip, Corner (T+R)")
      (fields
        (field (name "INTERNAL_PART_NUMBER") "MCD-02164")
        (field (name "MANUFACTURER") "HARWIN")
        (field (name "PROVIDED_BY") "SUBCO")
      )
      (libsource (lib "MCD_PARTS_database") (part "Shield-clip_S0951-46R"))
    )
    (comp (ref "U1")
      (value "BGS13S4N9")
      (footprint "ICC_TSNP-9-3_1P1X1P1_P040")
      (description "Wideband RF SP3T Switch")
      (fields
        (field (name "INTERNAL_PART_NUMBER") "MCD-02018")
        (field (name "MANUFACTURER") "INFINEON")
        (field (name "PROVIDED_BY") "SUBCO")
      )
      (libsource (lib "MCD_PARTS_database") (part "BGS13S4N9"))
    )
    (comp (ref "U3")
      (value "NX3L1T3157GM")
      (footprint "ICC_SOT886_XSON6")
      (description "DC switch - Ultra-Low 0.5ohm  SPDT analog switch")
      (fields
        (field (name "INTERNAL_PART_NUMBER") "MCD-01514")
        (field (name "MANUFACTURER") "NXP")
        (field (name "PROVIDED_BY") "SUBCO")
      )
      (libsource (lib "") (part "NX3L1T3157GM_1"))
    )
    (comp (ref "U4")
      (value "NX3L1T3157GM")
      (footprint "ICC_SOT886_XSON6")
      (description "DC switch - Ultra-Low 0.5ohm  SPDT analog switch")
      (fields
        (field (name "INTERNAL_PART_NUMBER") "MCD-01514")
        (field (name "MANUFACTURER") "NXP")
        (field (name "PROVIDED_BY") "SUBCO")
      )
      (libsource (lib "MCD_PARTS_database") (part "NX3L1T3157GM"))
    )
    (comp (ref "U6")
      (value "STM32WL55JCI7")
      (footprint "ICC_UFBGA73_5X5_P050")
      (description "Multiprotocol Wireless 32-bit MCUwith LPWAN Sub-GHz radio solution")
      (fields
        (field (name "INTERNAL_PART_NUMBER") "MCD-01435")
        (field (name "MANUFACTURER") "STMICROELECTRONICS")
      )
      (libsource (lib "MCD_PARTS_database") (part "STM32WL5x_BGA73"))
    )
    (comp (ref "X3")
      (value "NX2016SA 32MHz")
      (footprint "CRY_NX2016SA_4P")
      (description "Crystal 32MHz, 10pF, +-10 ppm, 50ohm max, SMD")
      (fields
        (field (name "INTERNAL_PART_NUMBER") "MCD-01507")
        (field (name "MANUFACTURER_PART_NUMBER") "NX2016SA 32MHz EXS00A-CS06465")
        (field (name "PROVIDED_BY") "SUBCO")
      )
      (libsource (lib "MCD_PARTS_database") (part "XTAL_4_PINS"))
    )
    (comp (ref "X4")
      (value "32MHz")
      (footprint "CRY_NDK_NT2016SB_4P")
      (description "NT2016SF-32M-END5875A")
      (fields
        (field (name "INTERNAL_PART_NUMBER") "MCD-02240")
        (field (name "MANUFACTURER") "NDK")
        (field (name "MANUFACTURER_PART_NUMBER") "NT2016SF-32M-END5875A")
      )
      (libsource (lib "MCD_PARTS_database") (part "NT2016SB"))
    )
  )
  (nets
    (net (code "1") (name "/FE_CTRL1") (class "Default")
      (node (ref "R27") (pin "1") (pinfunction "1_1") (pintype "passive"))
      (node (ref "U3") (pin "6") (pinfunction "SEL_6") (pintype "passive"))
      (node (ref "U4") (pin "6") (pinfunction "SEL_6") (pintype "passive"))
    )
    (net (code "2") (name "/FE_CTRL2") (class "Default")
      (node (ref "R28") (pin "1") (pinfunction "1_1") (pintype "passive"))
    )
    (net (code "3") (name "/FE_CTRL3") (class "Default")
      (node (ref "SB18") (pin "2") (pinfunction "2_2") (pintype "passive"))
    )
    (net (code "4") (name "/PB0") (class "Default")
      (node (ref "SB20") (pin "1") (pinfunction "1_1") (pintype "passive"))
      (node (ref "U6") (pin "F6") (pinfunction "PB0-VDD_TCXO_F6") (pintype "passive"))
    )
    (net (code "5") (name "/RFI_N") (class "Default")
      (node (ref "C19") (pin "2") (pinfunction "2_2") (pintype "passive"))
      (node (ref "L11") (pin "1") (pinfunction "1_1") (pintype "passive"))
      (node (ref "U6") (pin "H7") (pinfunction "RFI_N_H7") (pintype "passive"))
    )
    (net (code "6") (name "/RFI_P") (class "Default")
      (node (ref "C20") (pin "1") (pinfunction "1_1") (pintype "passive"))
      (node (ref "L11") (pin "2") (pinfunction "2_2") (pintype "passive"))
      (node (ref "U6") (pin "J6") (pinfunction "RFI_P_J6") (pintype "passive"))
    )
    (net (code "7") (name "/XTA") (class "Default")
      (node (ref "C31") (pin "2") (pinfunction "2_2") (pintype "passive"))
      (node (ref "R39") (pin "1") (pinfunction "1_1") (pintype "passive"))
      (node (ref "R41") (pin "2") (pinfunction "2_2") (pintype "passive"))
      (node (ref "U6") (pin "G9") (pinfunction "OSC_IN_G9") (pintype "passive"))
    )
    (net (code "8") (name "GND") (class "Default")
      (node (ref "C11") (pin "1") (pinfunction "1_1") (pintype "passive"))
      (node (ref "C14") (pin "1") (pinfunction "1_1") (pintype "passive"))
      (node (ref "C17") (pin "1") (pinfunction "1_1") (pintype "passive"))
      (node (ref "C19") (pin "1") (pinfunction "1_1") (pintype "passive"))
      (node (ref "C21") (pin "1") (pinfunction "1_1") (pintype "passive"))
      (node (ref "C22") (pin "1") (pinfunction "1_1") (pintype "passive"))
      (node (ref "C24") (pin "2") (pinfunction "2_2") (pintype "passive"))
      (node (ref "C25") (pin "1") (pinfunction "1_1") (pintype "passive"))
      (node (ref "C27") (pin "1") (pinfunction "1_1") (pintype "passive"))
      (node (ref "C30") (pin "1") (pinfunction "1_1") (pintype "passive"))
      (node (ref "C35") (pin "1") (pinfunction "1_1") (pintype "passive"))
      (node (ref "C37") (pin "2") (pinfunction "2_2") (pintype "passive"))
      (node (ref "C38") (pin "1") (pinfunction "1_1") (pintype "passive"))
      (node (ref "C5") (pin "1") (pinfunction "1_1") (pintype "passive"))
      (node (ref "C6") (pin "1") (pinfunction "1_1") (pintype "passive"))
      (node (ref "C7") (pin "1") (pinfunction "1_1") (pintype "passive"))
      (node (ref "C71") (pin "1") (pinfunction "1_1") (pintype "passive"))
      (node (ref "C72") (pin "1") (pinfunction "1_1") (pintype "passive"))
      (node (ref "C73") (pin "1") (pinfunction "1_1") (pintype "passive"))
      (node (ref "C74") (pin "1") (pinfunction "1_1") (pintype "passive"))
      (node (ref "C76") (pin "1") (pinfunction "1_1") (pintype "passive"))
      (node (ref "C77") (pin "2") (pinfunction "2_2") (pintype "passive"))
      (node (ref "C78") (pin "1") (pinfunction "1_1") (pintype "passive"))
      (node (ref "C79") (pin "1") (pinfunction "1_1") (pintype "passive"))
      (node (ref "C8") (pin "1") (pinfunction "1_1") (pintype "passive"))
      (node (ref "C80") (pin "1") (pinfunction "1_1") (pintype "passive"))
      (node (ref "C82") (pin "1") (pinfunction "1_1") (pintype "passive"))
      (node (ref "C85") (pin "1") (pinfunction "1_1") (pintype "passive"))
      (node (ref "C92") (pin "1") (pinfunction "1_1") (pintype "passive"))
      (node (ref "C93") (pin "1") (pinfunction "1_1") (pintype "passive"))
      (node (ref "CN12") (pin "2") (pinfunction "GND_2") (pintype "passive"))
      (node (ref "CN12") (pin "3") (pinfunction "GND_3") (pintype "passive"))
      (node (ref "CN12") (pin "4") (pinfunction "GND_4") (pintype "passive"))
      (node (ref "CN12") (pin "5") (pinfunction "GND_5") (pintype "passive"))
      (node (ref "CN13") (pin "2") (pinfunction "2_2") (pintype "passive"))
      (node (ref "R41") (pin "1") (pinfunction "1_1") (pintype "passive"))
      (node (ref "SC1") (pin "1") (pinfunction "1_1") (pintype "passive"))
      (node (ref "SC2") (pin "1") (pinfunction "1_1") (pintype "passive"))
      (node (ref "SC3") (pin "1") (pinfunction "1_1") (pintype "passive"))
      (node (ref "SC4") (pin "1") (pinfunction "1_1") (pintype "passive"))
      (node (ref "SC5") (pin "1") (pinfunction "1_1") (pintype "passive"))
      (node (ref "SC6") (pin "1") (pinfunction "1_1") (pintype "passive"))
      (node (ref "SC7") (pin "1") (pinfunction "1_1") (pintype "passive"))
      (node (ref "SC8") (pin "1") (pinfunction "1_1") (pintype "passive"))
      (node (ref "SC9") (pin "1") (pinfunction "1_1") (pintype "passive"))
      (node (ref "U1") (pin "6") (pinfunction "DGND_6") (pintype "passive"))
      (node (ref "U1") (pin "9") (pinfunction "GND_9") (pintype "passive"))
      (node (ref "U3") (pin "2") (pinfunction "GND_2") (pintype "passive"))
      (node (ref "U4") (pin "2") (pinfunction "GND_2") (pintype "passive"))
      (node (ref "U6") (pin "A1") (pinfunction "VSSSMPS_A1") (pintype "passive"))
      (node (ref "U6") (pin "G6") (pinfunction "VSSRF_G6") (pintype "passive"))
      (node (ref "U6") (pin "G7") (pinfunction "VSSRF_G7") (pintype "passive"))
      (node (ref "U6") (pin "G8") (pinfunction "VSSRF_G8") (pintype "passive"))
      (node (ref "U6") (pin "H6") (pinfunction "VSSRF_H6") (pintype "passive"))
      (node (ref "X3") (pin "2") (pinfunction "2_2") (pintype "passive"))
      (node (ref "X3") (pin "4") (pinfunction "4_4") (pintype "passive"))
      (node (ref "X4") (pin "1") (pinfunction "EN_1") (pintype "passive"))
      (node (ref "X4") (pin "2") (pinfunction "GND_2") (pintype "passive"))
    )
    (net (code "9") (name "Net-(C2-Pad1)") (class "Default")
      (node (ref "C2") (pin "1") (pinfunction "1_1") (pintype "passive"))
      (node (ref "C6") (pin "2") (pinfunction "2_2") (pintype "passive"))
      (node (ref "L2") (pin "2") (pinfunction "2_2") (pintype "passive"))
    )
    (net (code "10") (name "Net-(C11-Pad2)") (class "Default")
      (node (ref "C11") (pin "2") (pinfunction "2_2") (pintype "passive"))
      (node (ref "C12") (pin "1") (pinfunction "1_1") (pintype "passive"))
      (node (ref "C15") (pin "2") (pinfunction "2_2") (pintype "passive"))
      (node (ref "L5") (pin "2") (pinfunction "2_2") (pintype "passive"))
    )
    (net (code "11") (name "Net-(C12-Pad2)") (class "Default")
      (node (ref "C12") (pin "2") (pinfunction "2_2") (pintype "passive"))
      (node (ref "L3") (pin "1") (pinfunction "1_1") (pintype "passive"))
    )
    (net (code "12") (name "Net-(C13-Pad1)") (class "Default")
      (node (ref "C13") (pin "1") (pinfunction "1_1") (pintype "passive"))
      (node (ref "L4") (pin "1") (pinfunction "1_1") (pintype "passive"))
    )
    (net (code "13") (name "Net-(C13-Pad2)") (class "Default")
      (node (ref "C13") (pin "2") (pinfunction "2_2") (pintype "passive"))
      (node (ref "C14") (pin "2") (pinfunction "2_2") (pintype "passive"))
      (node (ref "C16") (pin "1") (pinfunction "1_1") (pintype "passive"))
      (node (ref "L6") (pin "2") (pinfunction "2_2") (pintype "passive"))
    )
    (net (code "14") (name "Net-(C15-Pad1)") (class "Default")
      (node (ref "C15") (pin "1") (pinfunction "1_1") (pintype "passive"))
      (node (ref "C22") (pin "2") (pinfunction "2_2") (pintype "passive"))
      (node (ref "L5") (pin "1") (pinfunction "1_1") (pintype "passive"))
      (node (ref "L7") (pin "2") (pinfunction "2_2") (pintype "passive"))
      (node (ref "L9") (pin "2") (pinfunction "2_2") (pintype "passive"))
    )
    (net (code "15") (name "Net-(C16-Pad2)") (class "Default")
      (node (ref "C16") (pin "2") (pinfunction "2_2") (pintype "passive"))
      (node (ref "C21") (pin "2") (pinfunction "2_2") (pintype "passive"))
      (node (ref "L10") (pin "2") (pinfunction "2_2") (pintype "passive"))
      (node (ref "L6") (pin "1") (pinfunction "1_1") (pintype "passive"))
      (node (ref "L8") (pin "2") (pinfunction "2_2") (pintype "passive"))
    )
    (net (code "16") (name "Net-(C30-Pad2)") (class "Default")
      (node (ref "C30") (pin "2") (pinfunction "2_2") (pintype "passive"))
      (node (ref "R39") (pin "2") (pinfunction "2_2") (pintype "passive"))
      (node (ref "X3") (pin "1") (pinfunction "1_1") (pintype "passive"))
    )
    (net (code "17") (name "Net-(C31-Pad1)") (class "Default")
      (node (ref "C31") (pin "1") (pinfunction "1_1") (pintype "passive"))
      (node (ref "R2") (pin "2") (pinfunction "2_2") (pintype "passive"))
    )
    (net (code "18") (name "Net-(C38-Pad2)") (class "Default")
      (node (ref "C38") (pin "2") (pinfunction "2_2") (pintype "passive"))
      (node (ref "R40") (pin "2") (pinfunction "2_2") (pintype "passive"))
      (node (ref "X3") (pin "3") (pinfunction "3_3") (pintype "passive"))
    )
    (net (code "19") (name "Net-(CN12-RF)") (class "Default")
      (node (ref "C5") (pin "2") (pinfunction "2_2") (pintype "passive"))
      (node (ref "CN12") (pin "1") (pinfunction "RF_1") (pintype "passive"))
      (node (ref "L2") (pin "1") (pinfunction "1_1") (pintype "passive"))
    )
    (net (code "20") (name "Net-(CN13-Pad1)") (class "Default")
      (node (ref "CN13") (pin "1") (pinfunction "1_1") (pintype "passive"))
      (node (ref "R33") (pin "1") (pinfunction "1_1") (pintype "passive"))
    )
    (net (code "21") (name "Net-(L13-Pad2)") (class "Default")
      (node (ref "L13") (pin "2") (pinfunction "2_2") (pintype "passive"))
      (node (ref "R32") (pin "2") (pinfunction "2_2") (pintype "passive"))
      (node (ref "R33") (pin "2") (pinfunction "2_2") (pintype "passive"))
    )
    (net (code "22") (name "Net-(R29-Pad2)") (class "Default")
      (node (ref "R29") (pin "2") (pinfunction "2_2") (pintype "passive"))
      (node (ref "SB18") (pin "1") (pinfunction "1_1") (pintype "passive"))
    )
    (net (code "23") (name "Net-(U1-RF1)") (class "Default")
      (node (ref "C17") (pin "2") (pinfunction "2_2") (pintype "passive"))
      (node (ref "C20") (pin "2") (pinfunction "2_2") (pintype "passive"))
      (node (ref "U1") (pin "3") (pinfunction "RF1_3") (pintype "passive"))
    )
    (net (code "24") (name "Net-(U1-RF2)") (class "Default")
      (node (ref "C7") (pin "2") (pinfunction "2_2") (pintype "passive"))
      (node (ref "L3") (pin "2") (pinfunction "2_2") (pintype "passive"))
      (node (ref "U1") (pin "5") (pinfunction "RF2_5") (pintype "passive"))
    )
    (net (code "25") (name "Net-(U1-RF3)") (class "Default")
      (node (ref "C8") (pin "2") (pinfunction "2_2") (pintype "passive"))
      (node (ref "L4") (pin "2") (pinfunction "2_2") (pintype "passive"))
      (node (ref "U1") (pin "2") (pinfunction "RF3_2") (pintype "passive"))
    )
    (net (code "26") (name "Net-(U1-RFin)") (class "Default")
      (node (ref "C2") (pin "2") (pinfunction "2_2") (pintype "passive"))
      (node (ref "U1") (pin "4") (pinfunction "RFin_4") (pintype "passive"))
    )
    (net (code "27") (name "Net-(U1-V1)") (class "Default")
      (node (ref "C72") (pin "2") (pinfunction "2_2") (pintype "passive"))
      (node (ref "R27") (pin "2") (pinfunction "2_2") (pintype "passive"))
      (node (ref "U1") (pin "1") (pinfunction "V1_1") (pintype "passive"))
    )
    (net (code "28") (name "Net-(U1-V2)") (class "Default")
      (node (ref "C71") (pin "2") (pinfunction "2_2") (pintype "passive"))
      (node (ref "R28") (pin "2") (pinfunction "2_2") (pintype "passive"))
      (node (ref "U1") (pin "8") (pinfunction "V2_8") (pintype "passive"))
    )
    (net (code "29") (name "Net-(U1-VDD)") (class "Default")
      (node (ref "C73") (pin "2") (pinfunction "2_2") (pintype "passive"))
      (node (ref "R29") (pin "1") (pinfunction "1_1") (pintype "passive"))
      (node (ref "U1") (pin "7") (pinfunction "VDD_7") (pintype "passive"))
    )
    (net (code "30") (name "Net-(U3-Y0)") (class "Default")
      (node (ref "R37") (pin "1") (pinfunction "1_1") (pintype "passive"))
      (node (ref "U3") (pin "3") (pinfunction "Y0_3") (pintype "passive"))
    )
    (net (code "31") (name "Net-(U3-Y1)") (class "Default")
      (node (ref "R38") (pin "1") (pinfunction "1_1") (pintype "passive"))
      (node (ref "U3") (pin "1") (pinfunction "Y1_1") (pintype "passive"))
    )
    (net (code "32") (name "Net-(U4-Y0)") (class "Default")
      (node (ref "C24") (pin "1") (pinfunction "1_1") (pintype "passive"))
      (node (ref "L7") (pin "1") (pinfunction "1_1") (pintype "passive"))
      (node (ref "U4") (pin "3") (pinfunction "Y0_3") (pintype "passive"))
    )
    (net (code "33") (name "Net-(U4-Y1)") (class "Default")
      (node (ref "C25") (pin "2") (pinfunction "2_2") (pintype "passive"))
      (node (ref "L8") (pin "1") (pinfunction "1_1") (pintype "passive"))
      (node (ref "U4") (pin "1") (pinfunction "Y1_1") (pintype "passive"))
    )
    (net (code "34") (name "Net-(U4-Z)") (class "Default")
      (node (ref "C74") (pin "2") (pinfunction "2_2") (pintype "passive"))
      (node (ref "C76") (pin "2") (pinfunction "2_2") (pintype "passive"))
      (node (ref "C92") (pin "2") (pinfunction "2_2") (pintype "passive"))
      (node (ref "U4") (pin "4") (pinfunction "Z_4") (pintype "passive"))
      (node (ref "U6") (pin "H9") (pinfunction "VR_PA_H9") (pintype "passive"))
    )
    (net (code "35") (name "Net-(U6A-OSC_OUT)") (class "Default")
      (node (ref "R40") (pin "1") (pinfunction "1_1") (pintype "passive"))
      (node (ref "U6") (pin "F8") (pinfunction "OSC_OUT_F8") (pintype "passive"))
    )
    (net (code "36") (name "Net-(U6A-RFO_HP)") (class "Default")
      (node (ref "L9") (pin "1") (pinfunction "1_1") (pintype "passive"))
      (node (ref "U6") (pin "J9") (pinfunction "RFO_HP_J9") (pintype "passive"))
    )
    (net (code "37") (name "Net-(U6A-RFO_LP)") (class "Default")
      (node (ref "L10") (pin "1") (pinfunction "1_1") (pintype "passive"))
      (node (ref "U6") (pin "J8") (pinfunction "RFO_LP_J8") (pintype "passive"))
    )
    (net (code "38") (name "Net-(U6B-VFBSMPS)") (class "Default")
      (node (ref "C85") (pin "2") (pinfunction "2_2") (pintype "passive"))
      (node (ref "L13") (pin "1") (pinfunction "1_1") (pintype "passive"))
      (node (ref "SB22") (pin "2") (pinfunction "2_2") (pintype "passive"))
      (node (ref "U6") (pin "B2") (pinfunction "VFBSMPS_B2") (pintype "passive"))
    )
    (net (code "39") (name "Net-(U6B-VLXSMPS)") (class "Default")
      (node (ref "R32") (pin "1") (pinfunction "1_1") (pintype "passive"))
      (node (ref "U6") (pin "B1") (pinfunction "VLXSMPS_B1") (pintype "passive"))
    )
    (net (code "40") (name "Net-(X4-OUT)") (class "Default")
      (node (ref "R2") (pin "1") (pinfunction "1_1") (pintype "passive"))
      (node (ref "X4") (pin "3") (pinfunction "OUT_3") (pintype "passive"))
    )
    (net (code "41") (name "Net-(X4-VDD)") (class "Default")
      (node (ref "C27") (pin "2") (pinfunction "2_2") (pintype "passive"))
      (node (ref "L12") (pin "1") (pinfunction "1_1") (pintype "passive"))
      (node (ref "X4") (pin "4") (pinfunction "VDD_4") (pintype "passive"))
    )
    (net (code "42") (name "PB0_VDD_TCXO") (class "Default")
      (node (ref "C77") (pin "1") (pinfunction "1_1") (pintype "passive"))
      (node (ref "C79") (pin "2") (pinfunction "2_2") (pintype "passive"))
      (node (ref "L12") (pin "2") (pinfunction "2_2") (pintype "passive"))
      (node (ref "SB20") (pin "2") (pinfunction "2_2") (pintype "passive"))
    )
    (net (code "43") (name "VDDPA") (class "Default")
      (node (ref "C78") (pin "2") (pinfunction "2_2") (pintype "passive"))
      (node (ref "U3") (pin "4") (pinfunction "Z_4") (pintype "passive"))
      (node (ref "U6") (pin "H8") (pinfunction "VDDPA_H8") (pintype "passive"))
    )
    (net (code "44") (name "VDDRF") (class "Default")
      (node (ref "C82") (pin "2") (pinfunction "2_2") (pintype "passive"))
      (node (ref "C93") (pin "2") (pinfunction "2_2") (pintype "passive"))
      (node (ref "R37") (pin "2") (pinfunction "2_2") (pintype "passive"))
      (node (ref "SB23") (pin "1") (pinfunction "1_1") (pintype "passive"))
      (node (ref "U6") (pin "E8") (pinfunction "VDDRF_E8") (pintype "passive"))
    )
    (net (code "45") (name "VDDRF1V55") (class "Default")
      (node (ref "C80") (pin "2") (pinfunction "2_2") (pintype "passive"))
      (node (ref "R38") (pin "2") (pinfunction "2_2") (pintype "passive"))
      (node (ref "SB22") (pin "1") (pinfunction "1_1") (pintype "passive"))
      (node (ref "U6") (pin "F7") (pinfunction "VDDRF1V55_F7") (pintype "passive"))
    )
    (net (code "46") (name "VDD_APP") (class "Default")
      (node (ref "U3") (pin "5") (pinfunction "VCC_5") (pintype "passive"))
      (node (ref "U4") (pin "5") (pinfunction "VCC_5") (pintype "passive"))
    )
    (net (code "47") (name "VDD_RF") (class "Default")
      (node (ref "C35") (pin "2") (pinfunction "2_2") (pintype "passive"))
      (node (ref "C37") (pin "1") (pinfunction "1_1") (pintype "passive"))
      (node (ref "SB23") (pin "2") (pinfunction "2_2") (pintype "passive"))
      (node (ref "U6") (pin "A2") (pinfunction "VDDSMPS_A2") (pintype "passive"))
    )
  )
)
